# Sheet3.net
KiCad netlist of a schematic drawn in Altium Designer
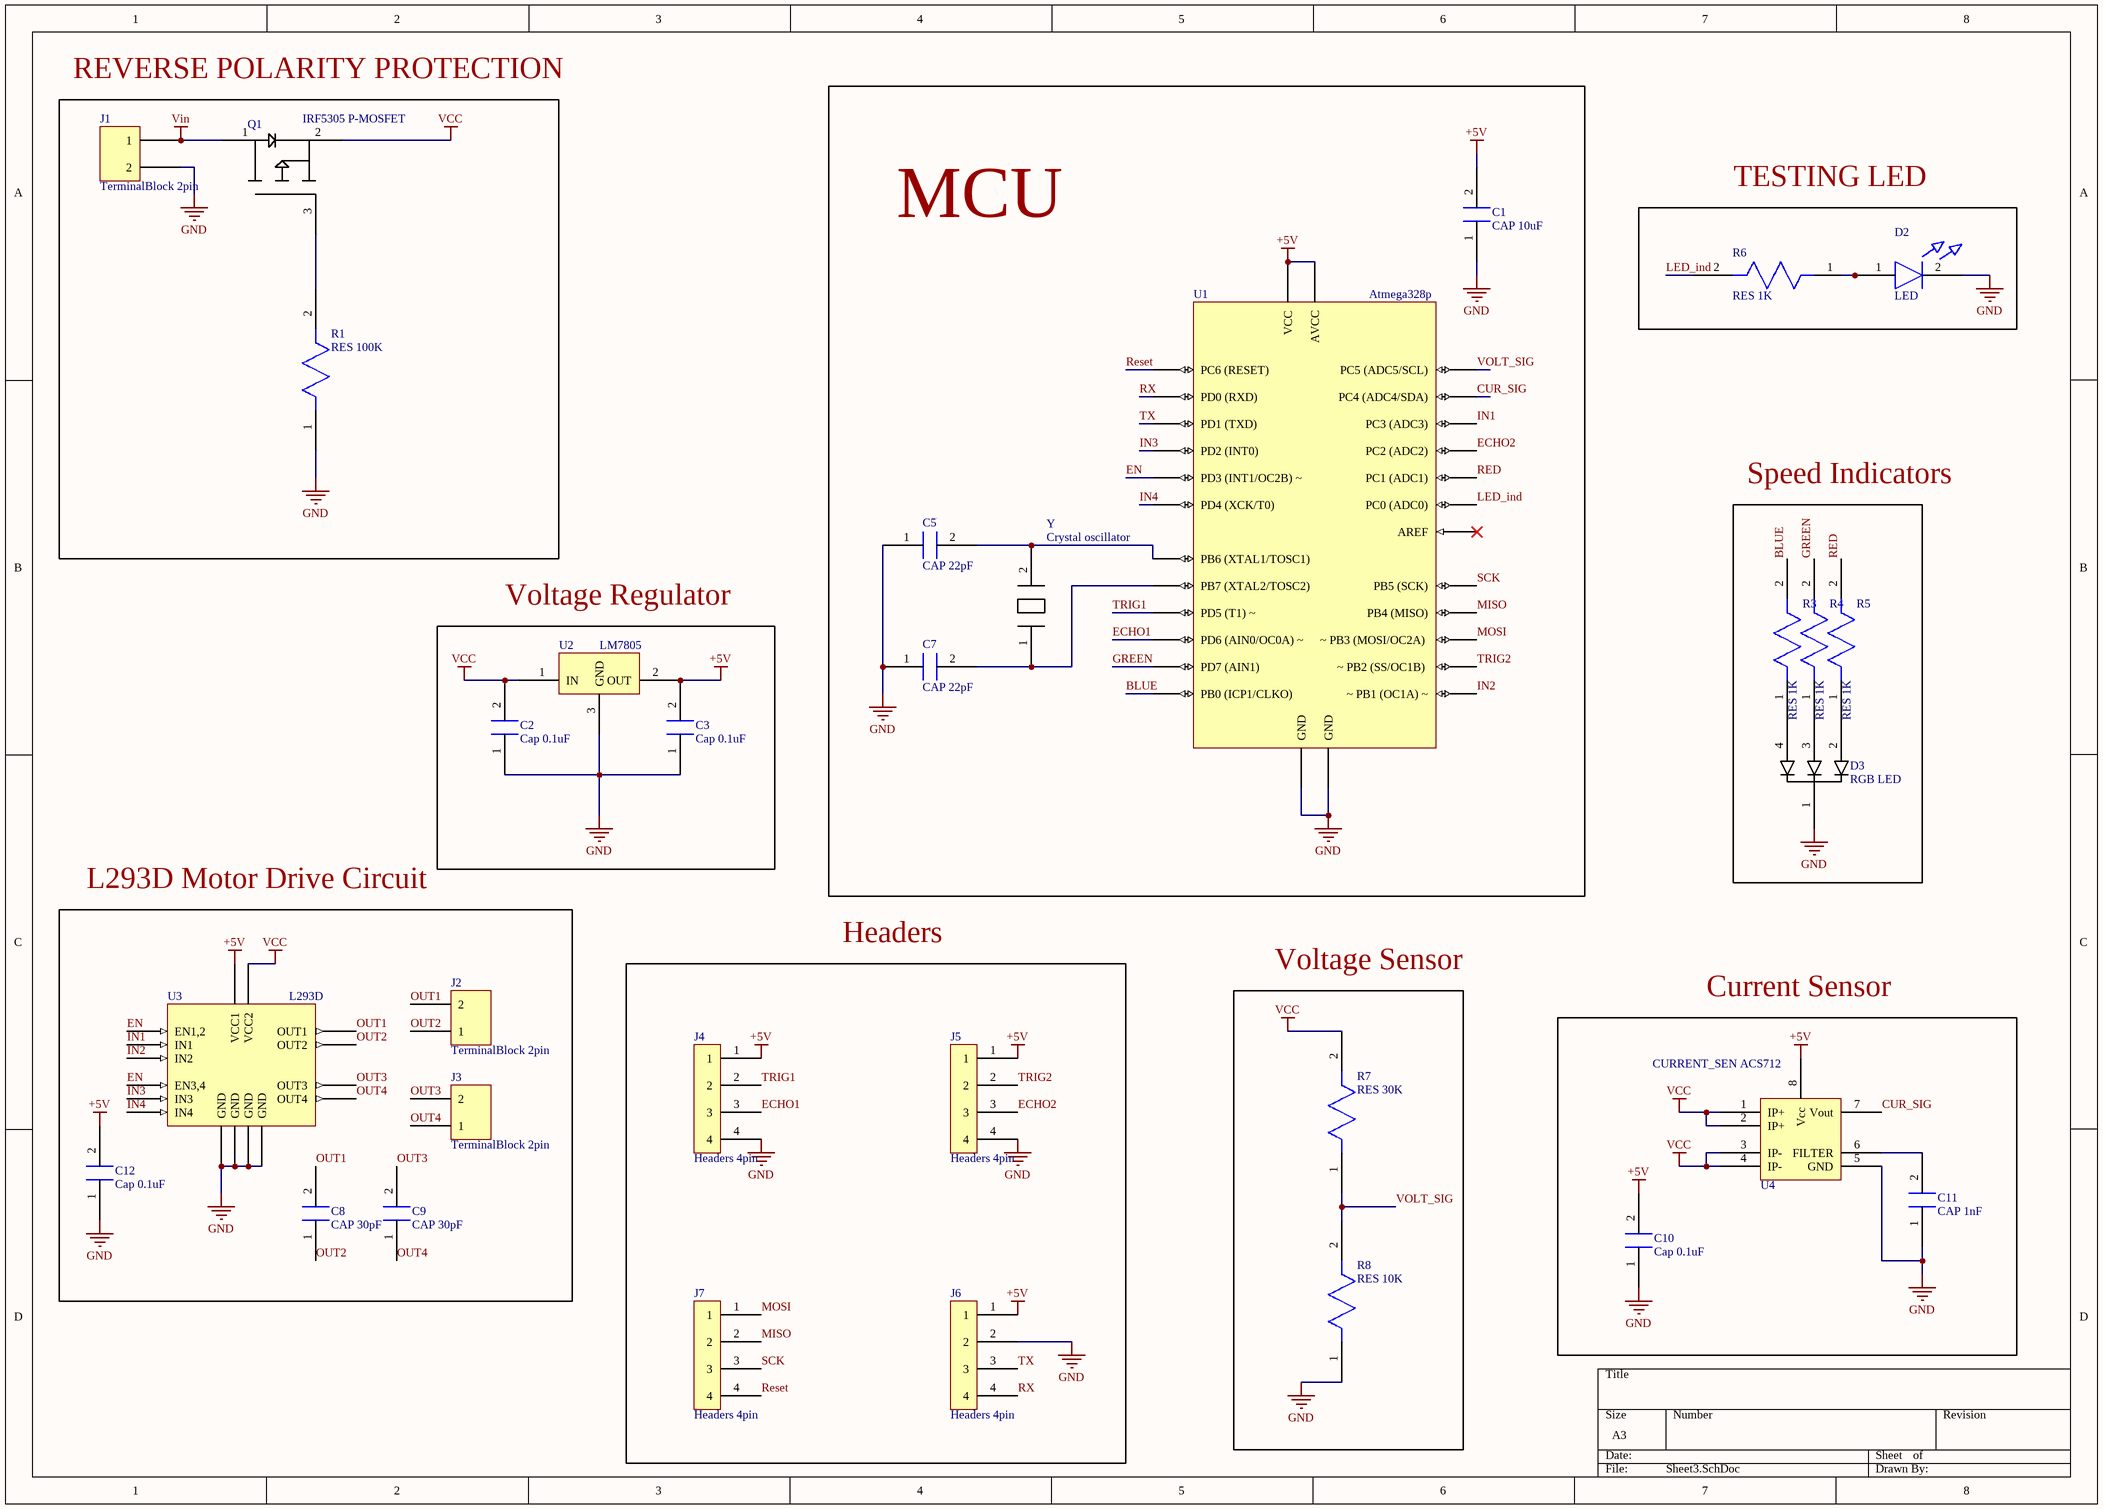
[diagram p0: Sheet3.SchDoc]

(export (version "E")
  (design (tool "Eeschema 10.0.6"))
  (components
    (comp (ref "C1") (value "CAP 10uF") (footprint "Cap 10uF") (libsource (lib "Schlib1") (part "CAP 10uF")))
    (comp (ref "C2")
      (value "Cap 0.1uF")
      (footprint "CAP 0.1uF")
      (libsource (lib "Schlib1") (part "Cap 0.1uF"))
    )
    (comp (ref "C3")
      (value "Cap 0.1uF")
      (footprint "CAP 0.1uF")
      (libsource (lib "Schlib1") (part "Cap 0.1uF"))
    )
    (comp (ref "C5") (value "CAP 22pF") (footprint "Cap 22pF") (libsource (lib "Schlib1") (part "CAP 22pF")))
    (comp (ref "C7") (value "CAP 22pF") (footprint "Cap 22pF") (libsource (lib "Schlib1") (part "CAP 22pF")))
    (comp (ref "C8") (value "CAP 30pF") (footprint "CAP 30pF") (libsource (lib "Schlib1") (part "CAP 30pF")))
    (comp (ref "C9") (value "CAP 30pF") (footprint "CAP 30pF") (libsource (lib "Schlib1") (part "CAP 30pF")))
    (comp (ref "C10")
      (value "Cap 0.1uF")
      (footprint "CAP 0.1uF")
      (libsource (lib "Schlib1") (part "Cap 0.1uF"))
    )
    (comp (ref "C11") (value "CAP 1nF") (footprint "CAP 1nF") (libsource (lib "Schlib1") (part "CAP 1nF")))
    (comp (ref "C12")
      (value "Cap 0.1uF")
      (footprint "CAP 0.1uF")
      (libsource (lib "Schlib1") (part "Cap 0.1uF"))
    )
    (comp (ref "D2") (value "LED") (footprint "LED") (libsource (lib "Schlib1") (part "LED")))
    (comp (ref "D3") (value "RGB LED") (footprint "RGB LED") (libsource (lib "Schlib1") (part "RGB LED")))
    (comp (ref "J1")
      (value "TerminalBlock 2pin")
      (footprint "Terminal Block 2pin")
      (libsource (lib "Schlib1") (part "TerminalBlock 2pin"))
    )
    (comp (ref "J2")
      (value "TerminalBlock 2pin")
      (footprint "Terminal Block 2pin")
      (libsource (lib "") (part "TerminalBlock 2pin_1"))
    )
    (comp (ref "J3")
      (value "TerminalBlock 2pin")
      (footprint "Terminal Block 2pin")
      (libsource (lib "") (part "TerminalBlock 2pin_1"))
    )
    (comp (ref "J4")
      (value "Headers 4pin")
      (footprint "Header 4pin")
      (libsource (lib "Schlib1") (part "Headers 4pin"))
    )
    (comp (ref "J5")
      (value "Headers 4pin")
      (footprint "Header 4pin")
      (libsource (lib "Schlib1") (part "Headers 4pin"))
    )
    (comp (ref "J6")
      (value "Headers 4pin")
      (footprint "Header 4pin")
      (libsource (lib "Schlib1") (part "Headers 4pin"))
    )
    (comp (ref "J7")
      (value "Headers 4pin")
      (footprint "Header 4pin")
      (libsource (lib "Schlib1") (part "Headers 4pin"))
    )
    (comp (ref "Q1")
      (value "IRF5305 P-MOSFET")
      (footprint "IRF5305")
      (libsource (lib "Schlib1") (part "IRF5305 P-MOSFET"))
    )
    (comp (ref "R1") (value "RES 100K") (footprint "Res100K") (libsource (lib "Schlib1") (part "RES 100K")))
    (comp (ref "R3") (value "RES 1K") (footprint "Res 1K") (libsource (lib "Schlib1") (part "RES 1K")))
    (comp (ref "R4") (value "RES 1K") (footprint "Res 1K") (libsource (lib "Schlib1") (part "RES 1K")))
    (comp (ref "R5") (value "RES 1K") (footprint "Res 1K") (libsource (lib "Schlib1") (part "RES 1K")))
    (comp (ref "R6") (value "RES 1K") (footprint "Res 1K") (libsource (lib "Schlib1") (part "RES 1K")))
    (comp (ref "R7") (value "RES 30K") (footprint "Res100K") (libsource (lib "Schlib1") (part "RES 100K")))
    (comp (ref "R8") (value "RES 10K") (footprint "Res10K") (libsource (lib "Schlib1") (part "RES 10K")))
    (comp (ref "U1")
      (value "Atmega328p")
      (footprint "ATMega 328 P-PU - duplicate")
      (libsource (lib "Schlib1") (part "Atmega328p"))
    )
    (comp (ref "U2") (value "LM7805") (footprint "LM7805") (libsource (lib "Schlib1") (part "LM7805")))
    (comp (ref "U3") (value "L293D") (footprint "L293D") (libsource (lib "Schlib1") (part "L293D")))
    (comp (ref "U4")
      (value "CURRENT_SEN ACS712")
      (footprint "Cuurent_sens")
      (libsource (lib "Schlib1") (part "CURRENT_MOD ACS712"))
    )
    (comp (ref "Y")
      (value "Crystal oscillator")
      (footprint "Crrystal 16MHZ")
      (libsource (lib "Schlib1") (part "Crystal oscillator"))
    )
  )
  (nets
    (net (code "1") (name "+5V") (class "Default")
      (node (ref "C1") (pin "2") (pinfunction "2_2") (pintype "passive"))
      (node (ref "C10") (pin "2") (pinfunction "2_2") (pintype "passive"))
      (node (ref "C12") (pin "2") (pinfunction "2_2") (pintype "passive"))
      (node (ref "C3") (pin "2") (pinfunction "2_2") (pintype "passive"))
      (node (ref "J4") (pin "1") (pinfunction "1_1") (pintype "passive"))
      (node (ref "J5") (pin "1") (pinfunction "1_1") (pintype "passive"))
      (node (ref "J6") (pin "1") (pinfunction "1_1") (pintype "passive"))
      (node (ref "U1") (pin "20") (pinfunction "AVCC_20") (pintype "passive"))
      (node (ref "U1") (pin "7") (pinfunction "VCC_7") (pintype "passive"))
      (node (ref "U2") (pin "2") (pinfunction "OUT_2") (pintype "passive"))
      (node (ref "U3") (pin "16") (pinfunction "VCC1_16") (pintype "power_in"))
      (node (ref "U4") (pin "8") (pinfunction "Vcc_8") (pintype "passive"))
    )
    (net (code "3") (name "/BLUE") (class "Default")
      (node (ref "R3") (pin "2") (pinfunction "4_2") (pintype "passive"))
      (node (ref "U1") (pin "14") (pinfunction "PB0_(ICP1/CLKO)_14") (pintype "bidirectional"))
    )
    (net (code "4") (name "/CUR_SIG") (class "Default")
      (node (ref "U1") (pin "27") (pinfunction "PC4_(ADC4/SDA)_27") (pintype "bidirectional"))
      (node (ref "U4") (pin "7") (pinfunction "Vout_7") (pintype "passive"))
    )
    (net (code "5") (name "/ECHO1") (class "Default")
      (node (ref "J4") (pin "3") (pinfunction "3_3") (pintype "passive"))
      (node (ref "U1") (pin "12") (pinfunction "PD6_(AIN0/OC0A)_~_12") (pintype "bidirectional"))
    )
    (net (code "6") (name "/ECHO2") (class "Default")
      (node (ref "J5") (pin "3") (pinfunction "3_3") (pintype "passive"))
      (node (ref "U1") (pin "25") (pinfunction "PC2_(ADC2)_25") (pintype "bidirectional"))
    )
    (net (code "7") (name "/EN") (class "Default")
      (node (ref "U1") (pin "5") (pinfunction "PD3_(INT1/OC2B)_~_5") (pintype "bidirectional"))
      (node (ref "U3") (pin "1") (pinfunction "EN1,2_1") (pintype "input"))
      (node (ref "U3") (pin "9") (pinfunction "EN3,4_9") (pintype "input"))
    )
    (net (code "8") (name "/GREEN") (class "Default")
      (node (ref "R4") (pin "2") (pinfunction "4_2") (pintype "passive"))
      (node (ref "U1") (pin "13") (pinfunction "PD7_(AIN1)_13") (pintype "bidirectional"))
    )
    (net (code "9") (name "/IN1") (class "Default")
      (node (ref "U1") (pin "26") (pinfunction "PC3_(ADC3)_26") (pintype "bidirectional"))
      (node (ref "U3") (pin "2") (pinfunction "IN1_2") (pintype "input"))
    )
    (net (code "10") (name "/IN2") (class "Default")
      (node (ref "U1") (pin "15") (pinfunction "~_PB1_(OC1A)_~_15") (pintype "bidirectional"))
      (node (ref "U3") (pin "7") (pinfunction "IN2_7") (pintype "input"))
    )
    (net (code "11") (name "/IN3") (class "Default")
      (node (ref "U1") (pin "4") (pinfunction "PD2_(INT0)_4") (pintype "bidirectional"))
      (node (ref "U3") (pin "10") (pinfunction "IN3_10") (pintype "input"))
    )
    (net (code "12") (name "/IN4") (class "Default")
      (node (ref "U1") (pin "6") (pinfunction "PD4_(XCK/T0)_6") (pintype "bidirectional"))
      (node (ref "U3") (pin "15") (pinfunction "IN4_15") (pintype "input"))
    )
    (net (code "13") (name "/LED_ind") (class "Default")
      (node (ref "R6") (pin "2") (pinfunction "4_2") (pintype "passive"))
      (node (ref "U1") (pin "23") (pinfunction "PC0_(ADC0)_23") (pintype "bidirectional"))
    )
    (net (code "14") (name "/MISO") (class "Default")
      (node (ref "J7") (pin "2") (pinfunction "2_2") (pintype "passive"))
      (node (ref "U1") (pin "18") (pinfunction "PB4_(MISO)_18") (pintype "bidirectional"))
    )
    (net (code "15") (name "/MOSI") (class "Default")
      (node (ref "J7") (pin "1") (pinfunction "1_1") (pintype "passive"))
      (node (ref "U1") (pin "17") (pinfunction "~_PB3_(MOSI/OC2A)_17") (pintype "bidirectional"))
    )
    (net (code "16") (name "/OUT1") (class "Default")
      (node (ref "C8") (pin "2") (pinfunction "2_2") (pintype "passive"))
      (node (ref "J2") (pin "2") (pinfunction "2_2") (pintype "passive"))
      (node (ref "U3") (pin "3") (pinfunction "OUT1_3") (pintype "output"))
    )
    (net (code "17") (name "/OUT2") (class "Default")
      (node (ref "C8") (pin "1") (pinfunction "1_1") (pintype "passive"))
      (node (ref "J2") (pin "1") (pinfunction "1_1") (pintype "passive"))
      (node (ref "U3") (pin "6") (pinfunction "OUT2_6") (pintype "output"))
    )
    (net (code "18") (name "/OUT3") (class "Default")
      (node (ref "C9") (pin "2") (pinfunction "2_2") (pintype "passive"))
      (node (ref "J3") (pin "2") (pinfunction "2_2") (pintype "passive"))
      (node (ref "U3") (pin "11") (pinfunction "OUT3_11") (pintype "output"))
    )
    (net (code "19") (name "/OUT4") (class "Default")
      (node (ref "C9") (pin "1") (pinfunction "1_1") (pintype "passive"))
      (node (ref "J3") (pin "1") (pinfunction "1_1") (pintype "passive"))
      (node (ref "U3") (pin "14") (pinfunction "OUT4_14") (pintype "output"))
    )
    (net (code "20") (name "/RED") (class "Default")
      (node (ref "R5") (pin "2") (pinfunction "4_2") (pintype "passive"))
      (node (ref "U1") (pin "24") (pinfunction "PC1_(ADC1)_24") (pintype "bidirectional"))
    )
    (net (code "21") (name "/RX") (class "Default")
      (node (ref "J6") (pin "4") (pinfunction "4_4") (pintype "passive"))
      (node (ref "U1") (pin "2") (pinfunction "PD0_(RXD)_2") (pintype "bidirectional"))
    )
    (net (code "22") (name "/Reset") (class "Default")
      (node (ref "J7") (pin "4") (pinfunction "4_4") (pintype "passive"))
      (node (ref "U1") (pin "1") (pinfunction "PC6_(RESET)_1") (pintype "bidirectional"))
    )
    (net (code "23") (name "/SCK") (class "Default")
      (node (ref "J7") (pin "3") (pinfunction "3_3") (pintype "passive"))
      (node (ref "U1") (pin "19") (pinfunction "PB5_(SCK)_19") (pintype "bidirectional"))
    )
    (net (code "24") (name "/TRIG1") (class "Default")
      (node (ref "J4") (pin "2") (pinfunction "2_2") (pintype "passive"))
      (node (ref "U1") (pin "11") (pinfunction "PD5_(T1)_~_11") (pintype "bidirectional"))
    )
    (net (code "25") (name "/TRIG2") (class "Default")
      (node (ref "J5") (pin "2") (pinfunction "2_2") (pintype "passive"))
      (node (ref "U1") (pin "16") (pinfunction "~_PB2_(SS/OC1B)_16") (pintype "bidirectional"))
    )
    (net (code "26") (name "/TX") (class "Default")
      (node (ref "J6") (pin "3") (pinfunction "3_3") (pintype "passive"))
      (node (ref "U1") (pin "3") (pinfunction "PD1_(TXD)_3") (pintype "bidirectional"))
    )
    (net (code "27") (name "/VOLT_SIG") (class "Default")
      (node (ref "R7") (pin "1") (pinfunction "3_1") (pintype "passive"))
      (node (ref "R8") (pin "2") (pinfunction "4_2") (pintype "passive"))
      (node (ref "U1") (pin "28") (pinfunction "PC5_(ADC5/SCL)_28") (pintype "bidirectional"))
    )
    (net (code "28") (name "GND") (class "Default")
      (node (ref "C1") (pin "1") (pinfunction "1_1") (pintype "passive"))
      (node (ref "C10") (pin "1") (pinfunction "1_1") (pintype "passive"))
      (node (ref "C11") (pin "1") (pinfunction "1_1") (pintype "passive"))
      (node (ref "C12") (pin "1") (pinfunction "1_1") (pintype "passive"))
      (node (ref "C2") (pin "1") (pinfunction "1_1") (pintype "passive"))
      (node (ref "C3") (pin "1") (pinfunction "1_1") (pintype "passive"))
      (node (ref "C5") (pin "1") (pinfunction "1_1") (pintype "passive"))
      (node (ref "C7") (pin "1") (pinfunction "1_1") (pintype "passive"))
      (node (ref "D2") (pin "2") (pinfunction "6_2") (pintype "passive"))
      (node (ref "D3") (pin "1") (pinfunction "(-)_1") (pintype "passive"))
      (node (ref "J1") (pin "2") (pinfunction "2_2") (pintype "passive"))
      (node (ref "J4") (pin "4") (pinfunction "4_4") (pintype "passive"))
      (node (ref "J5") (pin "4") (pinfunction "4_4") (pintype "passive"))
      (node (ref "J6") (pin "2") (pinfunction "2_2") (pintype "passive"))
      (node (ref "R1") (pin "1") (pinfunction "3_1") (pintype "passive"))
      (node (ref "R8") (pin "1") (pinfunction "3_1") (pintype "passive"))
      (node (ref "U1") (pin "22") (pinfunction "GND_22") (pintype "passive"))
      (node (ref "U1") (pin "8") (pinfunction "GND_8") (pintype "passive"))
      (node (ref "U2") (pin "3") (pinfunction "GND_3") (pintype "power_in"))
      (node (ref "U3") (pin "12") (pinfunction "GND_12") (pintype "power_in"))
      (node (ref "U3") (pin "13") (pinfunction "GND_13") (pintype "power_in"))
      (node (ref "U3") (pin "4") (pinfunction "GND_4") (pintype "power_in"))
      (node (ref "U3") (pin "5") (pinfunction "GND_5") (pintype "power_in"))
      (node (ref "U4") (pin "5") (pinfunction "GND_5") (pintype "passive"))
    )
    (net (code "29") (name "Net-(D2-7)") (class "Default")
      (node (ref "D2") (pin "1") (pinfunction "7_1") (pintype "passive"))
      (node (ref "R6") (pin "1") (pinfunction "3_1") (pintype "passive"))
    )
    (net (code "30") (name "Net-(D3-B)") (class "Default")
      (node (ref "D3") (pin "4") (pinfunction "B_4") (pintype "passive"))
      (node (ref "R3") (pin "1") (pinfunction "3_1") (pintype "passive"))
    )
    (net (code "31") (name "Net-(D3-G)") (class "Default")
      (node (ref "D3") (pin "3") (pinfunction "G_3") (pintype "passive"))
      (node (ref "R4") (pin "1") (pinfunction "3_1") (pintype "passive"))
    )
    (net (code "32") (name "Net-(D3-R)") (class "Default")
      (node (ref "D3") (pin "2") (pinfunction "R_2") (pintype "passive"))
      (node (ref "R5") (pin "1") (pinfunction "3_1") (pintype "passive"))
    )
    (net (code "33") (name "Net-(Q1-G)") (class "Default")
      (node (ref "Q1") (pin "3") (pinfunction "G_3") (pintype "passive"))
      (node (ref "R1") (pin "2") (pinfunction "4_2") (pintype "passive"))
    )
    (net (code "34") (name "Net-(U1-PB6_(XTAL1{slash}TOSC1))") (class "Default")
      (node (ref "C5") (pin "2") (pinfunction "2_2") (pintype "passive"))
      (node (ref "U1") (pin "9") (pinfunction "PB6_(XTAL1/TOSC1)_9") (pintype "bidirectional"))
      (node (ref "Y") (pin "2") (pinfunction "2_2") (pintype "passive"))
    )
    (net (code "35") (name "Net-(U1-PB7_(XTAL2{slash}TOSC2))") (class "Default")
      (node (ref "C7") (pin "2") (pinfunction "2_2") (pintype "passive"))
      (node (ref "U1") (pin "10") (pinfunction "PB7_(XTAL2/TOSC2)_10") (pintype "bidirectional"))
      (node (ref "Y") (pin "1") (pinfunction "1_1") (pintype "passive"))
    )
    (net (code "36") (name "Net-(U4-FILTER)") (class "Default")
      (node (ref "C11") (pin "2") (pinfunction "2_2") (pintype "passive"))
      (node (ref "U4") (pin "6") (pinfunction "FILTER_6") (pintype "passive"))
    )
    (net (code "37") (name "VCC") (class "Default")
      (node (ref "C2") (pin "2") (pinfunction "2_2") (pintype "passive"))
      (node (ref "Q1") (pin "2") (pinfunction "S_2") (pintype "passive"))
      (node (ref "R7") (pin "2") (pinfunction "4_2") (pintype "passive"))
      (node (ref "U2") (pin "1") (pinfunction "IN_1") (pintype "passive"))
      (node (ref "U3") (pin "8") (pinfunction "VCC2_8") (pintype "power_in"))
      (node (ref "U4") (pin "1") (pinfunction "IP+_1") (pintype "passive"))
      (node (ref "U4") (pin "2") (pinfunction "IP+_2") (pintype "passive"))
      (node (ref "U4") (pin "3") (pinfunction "IP-_3") (pintype "passive"))
      (node (ref "U4") (pin "4") (pinfunction "IP-_4") (pintype "passive"))
    )
    (net (code "38") (name "Vin") (class "Default")
      (node (ref "J1") (pin "1") (pinfunction "1_1") (pintype "passive"))
      (node (ref "Q1") (pin "1") (pinfunction "D_1") (pintype "passive"))
    )
    (net (code "39") (name "unconnected-(U1-AREF-Pad21)") (class "Default")
      (node (ref "U1") (pin "21") (pinfunction "AREF_21") (pintype "input+no_connect"))
    )
  )
)
